# Sch_TSAL.net
KiCad netlist of a schematic drawn in Altium Designer
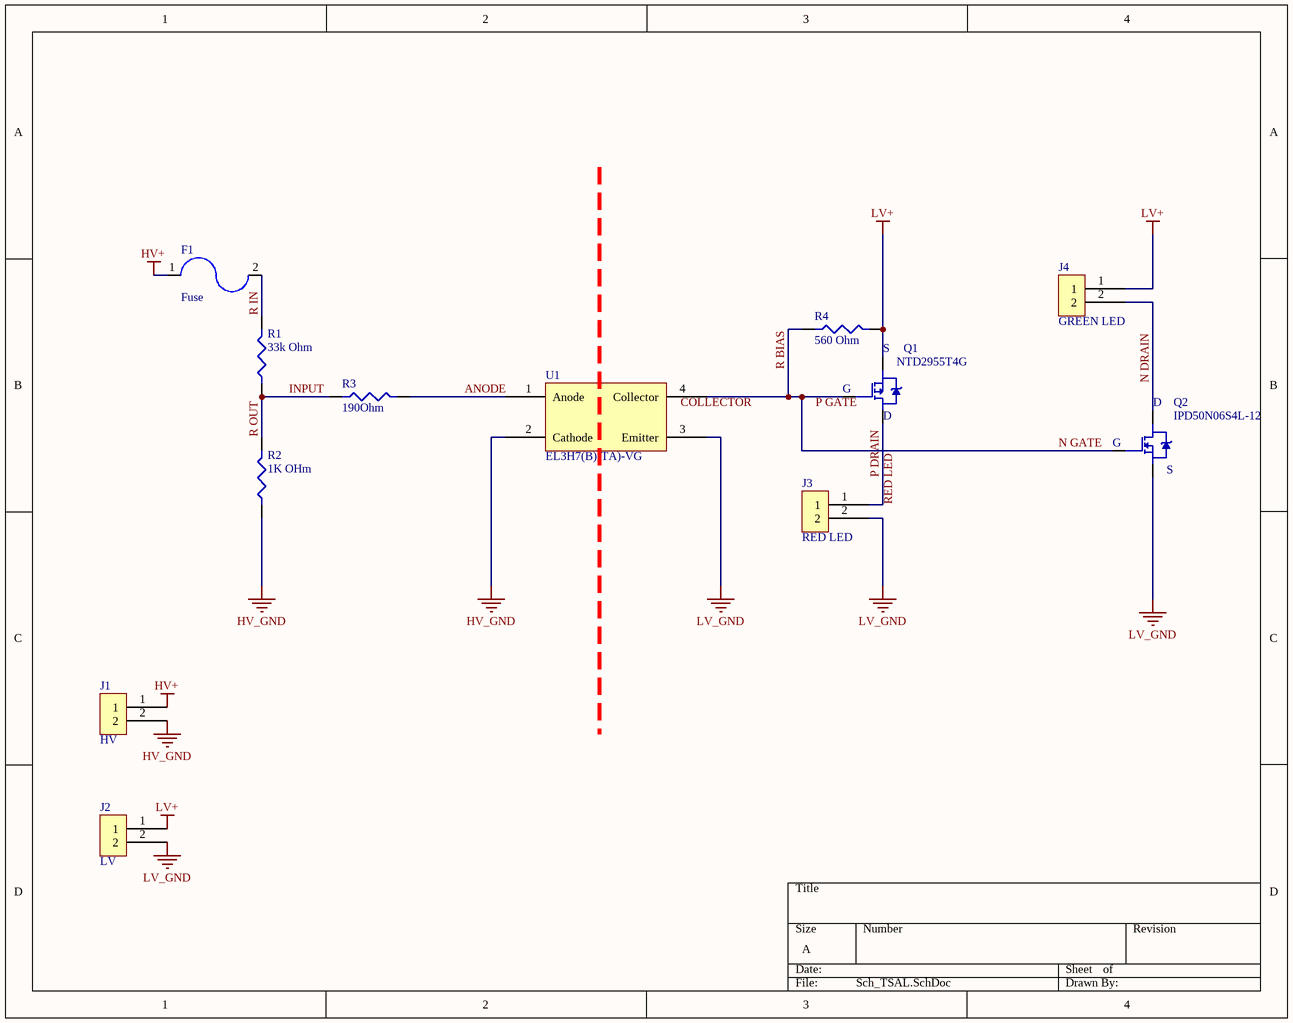
[diagram p0: Sch_TSAL.SchDoc]

(export (version "E")
  (design (tool "Eeschema 10.0.6"))
  (components
    (comp (ref "F1")
      (value "Fuse")
      (footprint "FUSE_SMD")
      (fields (field (name "MANUFACTURER") "Bel") (field (name "MANUFACTURER PART NUMBER") "0678D0800-02"))
      (libsource (lib "Schlib1_TSAL") (part "0678D0800-02"))
    )
    (comp (ref "J1")
      (value "HV")
      (footprint "2_PIN_CONNECTOR")
      (fields (field (name "MANUFACTURER") "Molex") (field (name "MANUFACTURER PART NUMBER") "0705530001"))
      (libsource (lib "Schlib1_TSAL") (part "0705530001"))
    )
    (comp (ref "J2")
      (value "LV")
      (footprint "2_PIN_CONNECTOR")
      (fields (field (name "MANUFACTURER") "Molex") (field (name "MANUFACTURER PART NUMBER") "0705530001"))
      (libsource (lib "Schlib1_TSAL") (part "0705530001"))
    )
    (comp (ref "J3")
      (value "RED LED")
      (footprint "2_PIN_CONNECTOR")
      (fields (field (name "MANUFACTURER") "Molex") (field (name "MANUFACTURER PART NUMBER") "0705530001"))
      (libsource (lib "Schlib1_TSAL") (part "0705530001"))
    )
    (comp (ref "J4")
      (value "GREEN LED")
      (footprint "2_PIN_CONNECTOR")
      (fields (field (name "MANUFACTURER") "Molex") (field (name "MANUFACTURER PART NUMBER") "0705530001"))
      (libsource (lib "Schlib1_TSAL") (part "0705530001"))
    )
    (comp (ref "Q1")
      (value "NTD2955T4G")
      (footprint "DPAK228P991X238-3N")
      (description "Trans MOSFET P-CH 60V 12A 3-Pin(2+Tab) DPAK T/R")
      (fields (field (name "MANUFACTURER") "ON Semiconductor"))
      (libsource (lib "Schlib1_TSAL") (part "NTD2955T4G"))
    )
    (comp (ref "Q2")
      (value "IPD50N06S4L-12")
      (footprint "DPAK228P998X235-3N")
      (description "MOSFET N-CH 60V 50A TO252-3-11")
      (fields (field (name "MANUFACTURER") "Infineon"))
      (libsource (lib "Schlib1_TSAL") (part "IPD50N06S4L-12"))
    )
    (comp (ref "R1")
      (value "33k Ohm")
      (footprint "RESC6332X07N")
      (description "RES SMD 33K OHM 5% 1W 2512")
      (fields
        (field (name "MANUFACTURER") "Stackpole Electronics")
        (field (name "MANUFACTURER PART NUMBER") "RMCF2512JT33K0")
      )
      (libsource (lib "Schlib1_TSAL") (part "RMCF2512JT33K0"))
    )
    (comp (ref "R2")
      (value "1K OHm")
      (footprint "RESC2012X06N")
      (description "RES 1K OHM 1% 1/4W 0805")
      (fields
        (field (name "MANUFACTURER") "Stackpole Electronics")
        (field (name "MANUFACTURER PART NUMBER") "RNCP0805FTD1K00")
      )
      (libsource (lib "Schlib1_TSAL") (part "RNCP0805FTD1K00"))
    )
    (comp (ref "R3")
      (value "190Ohm")
      (footprint "RESC2012X06N")
      (fields
        (field (name "MANUFACTURER") "Yageo")
        (field (name "MANUFACTURER PART NUMBER") "RC0805FR-0719R1L")
        (field (name "TOLERANCE") "1%")
      )
      (libsource (lib "Schlib1_TSAL") (part "RC0805FR-0719R1L"))
    )
    (comp (ref "R4")
      (value "560 Ohm")
      (footprint "RESC2012X06N")
      (description "RES SMD 560 OHM 5% 0.4W 0805")
      (fields (field (name "MANUFACTURER") "Rohm") (field (name "MANUFACTURER PART NUMBER") "ESR10EZPJ561"))
      (libsource (lib "Schlib1_TSAL") (part "ESR10EZPJ561"))
    )
    (comp (ref "U1")
      (value "EL3H7(B)(TA)-VG")
      (footprint "SOIC127P700X200-4N")
      (description "OPTOISOLATOR 3.75KV TRANS 4-SSOP")
      (fields (field (name "MANUFACTURER") "Everlight"))
      (libsource (lib "Schlib1_TSAL") (part "EL3H7(B)(TA)-VG"))
    )
  )
  (nets
    (net (code "1") (name "/ANODE") (class "Default")
      (node (ref "R3") (pin "2") (pinfunction "2_2") (pintype "passive"))
      (node (ref "U1") (pin "1") (pinfunction "Anode_1") (pintype "passive"))
    )
    (net (code "3") (name "/INPUT") (class "Default")
      (node (ref "R1") (pin "1") (pinfunction "1_1") (pintype "passive"))
      (node (ref "R2") (pin "2") (pinfunction "2_2") (pintype "passive"))
      (node (ref "R3") (pin "1") (pinfunction "1_1") (pintype "passive"))
    )
    (net (code "4") (name "/N DRAIN") (class "Default")
      (node (ref "J4") (pin "2") (pinfunction "2_2") (pintype "passive"))
      (node (ref "Q2") (pin "4") (pinfunction "4_4") (pintype "passive"))
    )
    (net (code "5") (name "/N GATE") (class "Default")
      (node (ref "Q1") (pin "1") (pinfunction "1_1") (pintype "passive"))
      (node (ref "Q2") (pin "1") (pinfunction "1_1") (pintype "passive"))
      (node (ref "R4") (pin "1") (pinfunction "1_1") (pintype "passive"))
      (node (ref "U1") (pin "4") (pinfunction "Collector_4") (pintype "passive"))
    )
    (net (code "6") (name "/P DRAIN") (class "Default")
      (node (ref "J3") (pin "1") (pinfunction "1_1") (pintype "passive"))
      (node (ref "Q1") (pin "3") (pinfunction "3_3") (pintype "passive"))
    )
    (net (code "8") (name "/R IN") (class "Default")
      (node (ref "F1") (pin "2") (pinfunction "2_2") (pintype "passive"))
      (node (ref "R1") (pin "2") (pinfunction "2_2") (pintype "passive"))
    )
    (net (code "10") (name "HV+") (class "Default")
      (node (ref "F1") (pin "1") (pinfunction "1_1") (pintype "passive"))
      (node (ref "J1") (pin "1") (pinfunction "1_1") (pintype "passive"))
    )
    (net (code "11") (name "HV_GND") (class "Default")
      (node (ref "J1") (pin "2") (pinfunction "2_2") (pintype "passive"))
      (node (ref "R2") (pin "1") (pinfunction "1_1") (pintype "passive"))
      (node (ref "U1") (pin "2") (pinfunction "Cathode_2") (pintype "passive"))
    )
    (net (code "12") (name "LV+") (class "Default")
      (node (ref "J2") (pin "1") (pinfunction "1_1") (pintype "passive"))
      (node (ref "J4") (pin "1") (pinfunction "1_1") (pintype "passive"))
      (node (ref "Q1") (pin "4") (pinfunction "4_4") (pintype "passive"))
      (node (ref "R4") (pin "2") (pinfunction "2_2") (pintype "passive"))
    )
    (net (code "13") (name "LV_GND") (class "Default")
      (node (ref "J2") (pin "2") (pinfunction "2_2") (pintype "passive"))
      (node (ref "J3") (pin "2") (pinfunction "2_2") (pintype "passive"))
      (node (ref "Q2") (pin "3") (pinfunction "3_3") (pintype "passive"))
      (node (ref "U1") (pin "3") (pinfunction "Emitter_3") (pintype "passive"))
    )
  )
)
